# jncc3000.net
KiCad netlist of a schematic drawn in EAGLE
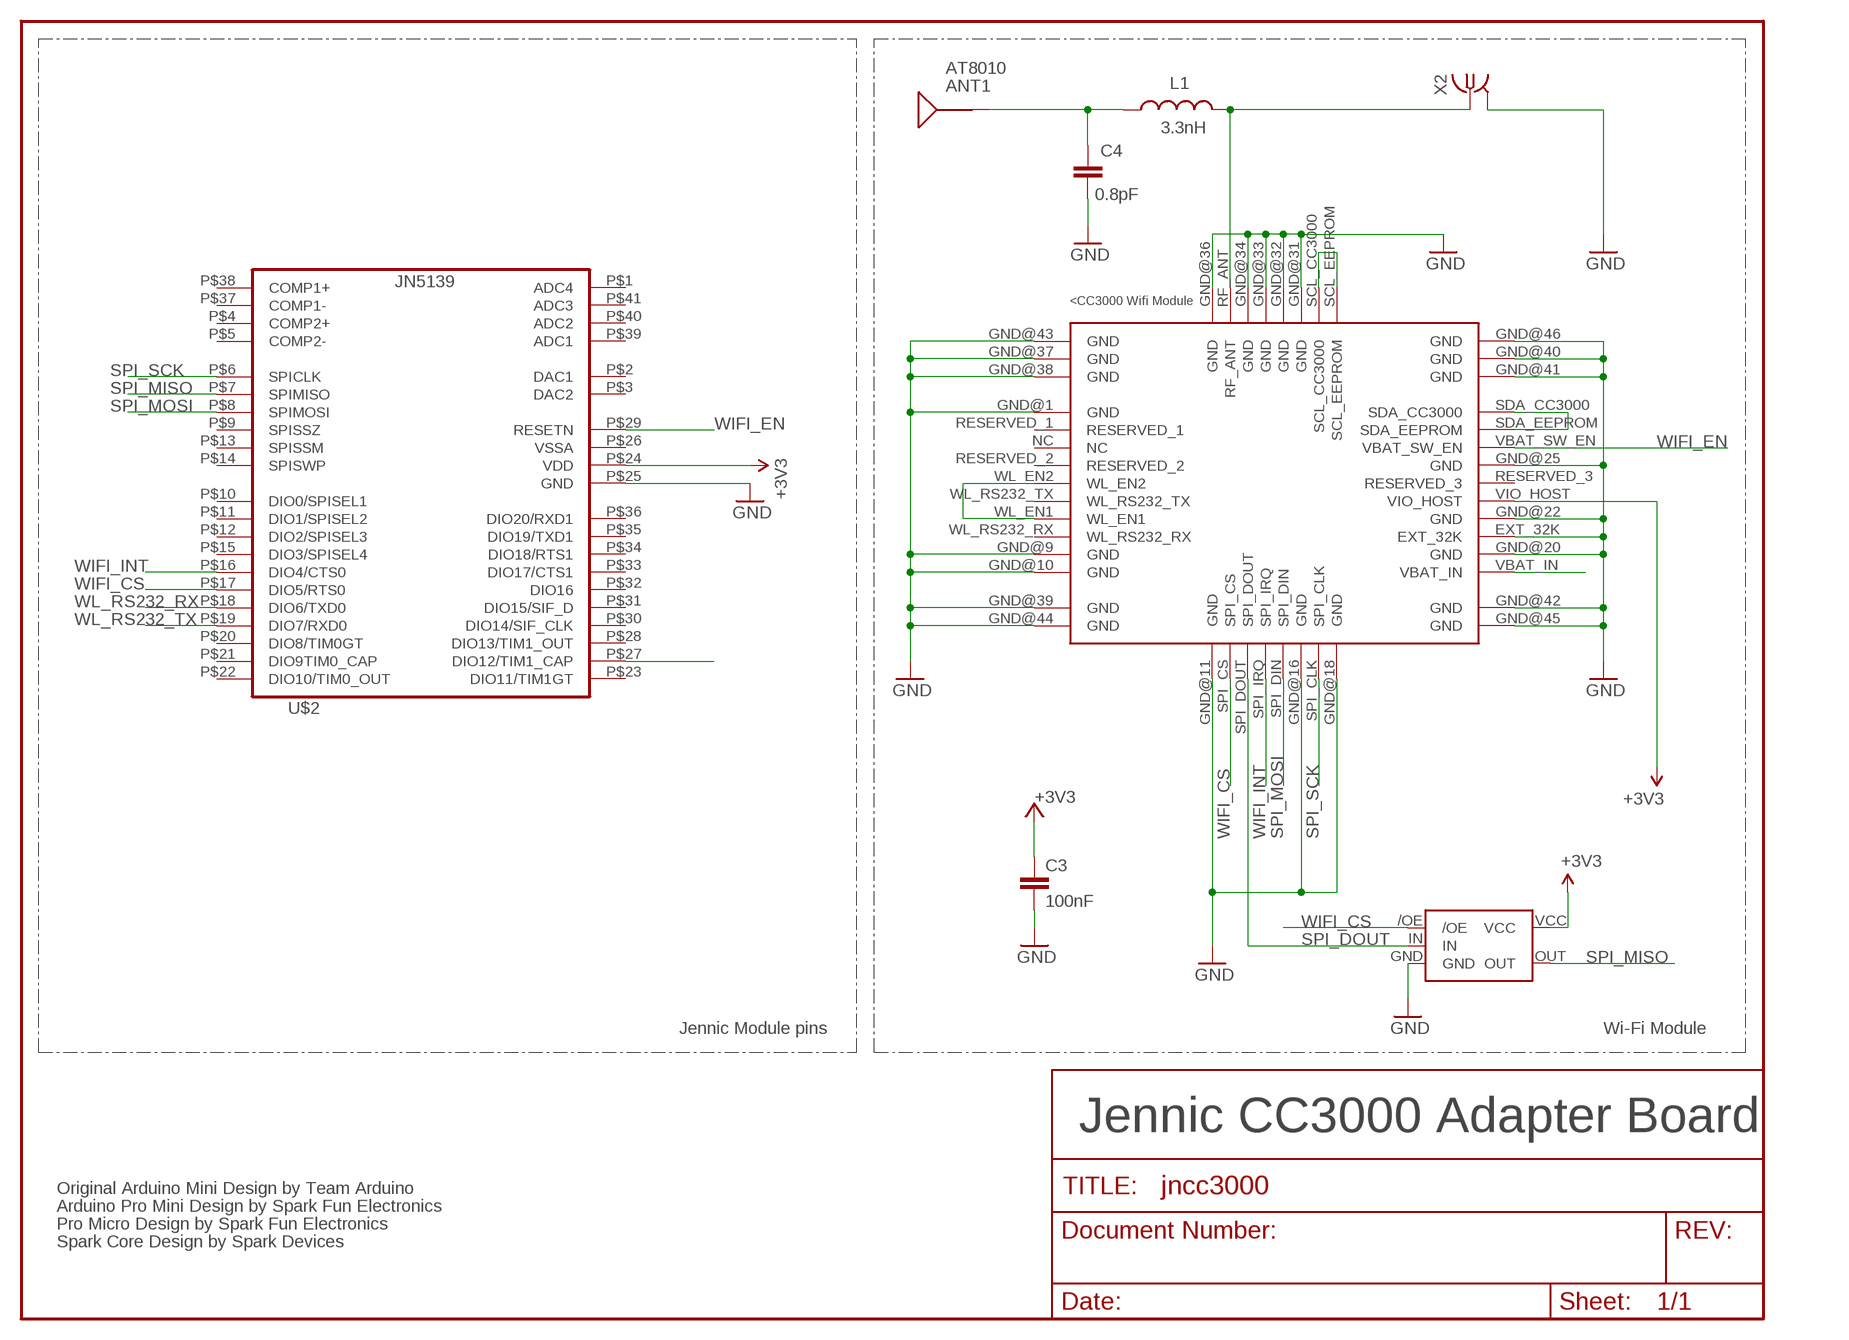
[diagram p0: schematic, sheet 1]

(export (version "E")
  (design (tool "Eeschema 10.0.6"))
  (components
    (comp (ref "ANT1")
      (value "AT8010")
      (footprint "eagle-import:AT8010")
      (libsource (lib "eagle-import") (part "AT8010"))
    )
    (comp (ref "C3")
      (value "100nF")
      (footprint "eagle-import:C0603")
      (libsource (lib "eagle-import") (part "C-EUC0603"))
    )
    (comp (ref "C4")
      (value "0.8pF")
      (footprint "eagle-import:C0603")
      (fields (field (name "COMMENT") "RF Capacitor"))
      (libsource (lib "eagle-import") (part "C-EUC0603"))
    )
    (comp (ref "L1")
      (value "3.3nH")
      (footprint "eagle-import:0603")
      (fields (field (name "COMMENT") "RF Inductor"))
      (libsource (lib "eagle-import") (part "INDUCTOR0603"))
    )
    (comp (ref "U$2")
      (value "JENNIC_JN51XXTH")
      (footprint "eagle-import:JN5139_TH")
      (libsource (lib "eagle-import") (part "JENNIC_JN51XXTH"))
    )
    (comp (ref "U1")
      (value "CC3000")
      (footprint "eagle-import:CC3000")
      (libsource (lib "eagle-import") (part "CC3000"))
    )
    (comp (ref "U4")
      (value "NL17SZ125SOT553")
      (footprint "eagle-import:SOT-553")
      (libsource (lib "eagle-import") (part "NL17SZ125SOT553"))
    )
    (comp (ref "X2")
      (value "IPEX-20279-001E")
      (footprint "eagle-import:IPEX-20279-001E")
      (libsource (lib "eagle-import") (part "IPEX-20279-001E"))
    )
  )
  (nets
    (net (code "1") (name "+3V3") (class "Default")
      (node (ref "C3") (pin "1") (pinfunction "1_1") (pintype "passive"))
      (node (ref "U$2") (pin "P$24") (pinfunction "VDD_P$24") (pintype "bidirectional"))
      (node (ref "U1") (pin "VIO_HOST") (pinfunction "VIO_HOST_VIO_HOST") (pintype "power_in"))
      (node (ref "U4") (pin "VCC") (pinfunction "VCC_VCC") (pintype "bidirectional"))
    )
    (net (code "2") (name "/SPI_DOUT") (class "Default")
      (node (ref "U1") (pin "SPI_DOUT") (pinfunction "SPI_DOUT_SPI_DOUT") (pintype "output"))
      (node (ref "U4") (pin "IN") (pinfunction "IN_IN") (pintype "bidirectional"))
    )
    (net (code "3") (name "/SPI_MISO") (class "Default")
      (node (ref "U$2") (pin "P$7") (pinfunction "SPIMISO_P$7") (pintype "bidirectional"))
      (node (ref "U4") (pin "OUT") (pinfunction "OUT_OUT") (pintype "bidirectional"))
    )
    (net (code "4") (name "/SPI_MOSI") (class "Default")
      (node (ref "U$2") (pin "P$8") (pinfunction "SPIMOSI_P$8") (pintype "bidirectional"))
      (node (ref "U1") (pin "SPI_DIN") (pinfunction "SPI_DIN_SPI_DIN") (pintype "input"))
    )
    (net (code "5") (name "/SPI_SCK") (class "Default")
      (node (ref "U$2") (pin "P$6") (pinfunction "SPICLK_P$6") (pintype "bidirectional"))
      (node (ref "U1") (pin "SPI_CLK") (pinfunction "SPI_CLK_SPI_CLK") (pintype "input"))
    )
    (net (code "6") (name "/VBAT") (class "Default")
      (node (ref "U$2") (pin "P$27") (pinfunction "DIO12/TIM1_CAP_P$27") (pintype "bidirectional"))
      (node (ref "U1") (pin "VBAT_IN") (pinfunction "VBAT_IN_VBAT_IN") (pintype "power_in"))
    )
    (net (code "7") (name "/WIFI_CS") (class "Default")
      (node (ref "U$2") (pin "P$17") (pinfunction "DIO5/RTS0_P$17") (pintype "bidirectional"))
      (node (ref "U1") (pin "SPI_CS") (pinfunction "SPI_CS_SPI_CS") (pintype "input"))
      (node (ref "U4") (pin "/OE") (pinfunction "/OE_/OE") (pintype "bidirectional"))
    )
    (net (code "8") (name "/WIFI_EN") (class "Default")
      (node (ref "U$2") (pin "P$29") (pinfunction "RESETN_P$29") (pintype "bidirectional"))
      (node (ref "U1") (pin "VBAT_SW_EN") (pinfunction "VBAT_SW_EN_VBAT_SW_EN") (pintype "input"))
    )
    (net (code "9") (name "/WIFI_INT") (class "Default")
      (node (ref "U$2") (pin "P$16") (pinfunction "DIO4/CTS0_P$16") (pintype "bidirectional"))
      (node (ref "U1") (pin "SPI_IRQ") (pinfunction "SPI_IRQ_SPI_IRQ") (pintype "output"))
    )
    (net (code "10") (name "/WL_RS232_RX") (class "Default")
      (node (ref "U$2") (pin "P$18") (pinfunction "DIO6/TXD0_P$18") (pintype "bidirectional"))
    )
    (net (code "11") (name "/WL_RS232_TX") (class "Default")
      (node (ref "U$2") (pin "P$19") (pinfunction "DIO7/RXD0_P$19") (pintype "bidirectional"))
    )
    (net (code "12") (name "GND") (class "Default")
      (node (ref "C3") (pin "2") (pinfunction "2_2") (pintype "passive"))
      (node (ref "C4") (pin "2") (pinfunction "2_2") (pintype "passive"))
      (node (ref "U$2") (pin "P$25") (pinfunction "GND_P$25") (pintype "bidirectional"))
      (node (ref "U1") (pin "EXT_32K") (pinfunction "EXT_32K_EXT_32K") (pintype "bidirectional"))
      (node (ref "U1") (pin "GND@1") (pinfunction "GND_GND@1") (pintype "power_in"))
      (node (ref "U1") (pin "GND@10") (pinfunction "GND_GND@10") (pintype "power_in"))
      (node (ref "U1") (pin "GND@11") (pinfunction "GND_GND@11") (pintype "power_in"))
      (node (ref "U1") (pin "GND@16") (pinfunction "GND_GND@16") (pintype "power_in"))
      (node (ref "U1") (pin "GND@18") (pinfunction "GND_GND@18") (pintype "power_in"))
      (node (ref "U1") (pin "GND@20") (pinfunction "GND_GND@20") (pintype "power_in"))
      (node (ref "U1") (pin "GND@22") (pinfunction "GND_GND@22") (pintype "power_in"))
      (node (ref "U1") (pin "GND@25") (pinfunction "GND_GND@25") (pintype "power_in"))
      (node (ref "U1") (pin "GND@31") (pinfunction "GND_GND@31") (pintype "power_in"))
      (node (ref "U1") (pin "GND@32") (pinfunction "GND_GND@32") (pintype "power_in"))
      (node (ref "U1") (pin "GND@33") (pinfunction "GND_GND@33") (pintype "power_in"))
      (node (ref "U1") (pin "GND@34") (pinfunction "GND_GND@34") (pintype "power_in"))
      (node (ref "U1") (pin "GND@36") (pinfunction "GND_GND@36") (pintype "power_in"))
      (node (ref "U1") (pin "GND@37") (pinfunction "GND_GND@37") (pintype "power_in"))
      (node (ref "U1") (pin "GND@38") (pinfunction "GND_GND@38") (pintype "power_in"))
      (node (ref "U1") (pin "GND@39") (pinfunction "GND_GND@39") (pintype "power_in"))
      (node (ref "U1") (pin "GND@40") (pinfunction "GND_GND@40") (pintype "power_in"))
      (node (ref "U1") (pin "GND@41") (pinfunction "GND_GND@41") (pintype "power_in"))
      (node (ref "U1") (pin "GND@42") (pinfunction "GND_GND@42") (pintype "power_in"))
      (node (ref "U1") (pin "GND@43") (pinfunction "GND_GND@43") (pintype "power_in"))
      (node (ref "U1") (pin "GND@44") (pinfunction "GND_GND@44") (pintype "power_in"))
      (node (ref "U1") (pin "GND@45") (pinfunction "GND_GND@45") (pintype "power_in"))
      (node (ref "U1") (pin "GND@46") (pinfunction "GND_GND@46") (pintype "power_in"))
      (node (ref "U1") (pin "GND@9") (pinfunction "GND_GND@9") (pintype "power_in"))
      (node (ref "U4") (pin "GND") (pinfunction "GND_GND") (pintype "bidirectional"))
      (node (ref "X2") (pin "2@1") (pinfunction "GND_2@1") (pintype "passive"))
      (node (ref "X2") (pin "2@2") (pinfunction "GND_2@2") (pintype "passive"))
    )
    (net (code "13") (name "Net-(ANT1-SIGNAL)") (class "Default")
      (node (ref "ANT1") (pin "SIG") (pinfunction "SIGNAL_SIG") (pintype "bidirectional"))
      (node (ref "C4") (pin "1") (pinfunction "1_1") (pintype "passive"))
      (node (ref "L1") (pin "1") (pinfunction "1_1") (pintype "passive"))
    )
    (net (code "14") (name "Net-(L1-Pad2)") (class "Default")
      (node (ref "L1") (pin "2") (pinfunction "2_2") (pintype "passive"))
      (node (ref "U1") (pin "RF_ANT") (pinfunction "RF_ANT_RF_ANT") (pintype "bidirectional"))
      (node (ref "X2") (pin "1") (pinfunction "1_1") (pintype "passive"))
    )
    (net (code "15") (name "Net-(U1-PadSCL_CC3000)") (class "Default")
      (node (ref "U1") (pin "SCL_CC3000") (pinfunction "SCL_CC3000_SCL_CC3000") (pintype "bidirectional"))
      (node (ref "U1") (pin "SCL_EEPROM") (pinfunction "SCL_EEPROM_SCL_EEPROM") (pintype "bidirectional"))
    )
    (net (code "16") (name "Net-(U1-PadSDA_CC3000)") (class "Default")
      (node (ref "U1") (pin "SDA_CC3000") (pinfunction "SDA_CC3000_SDA_CC3000") (pintype "bidirectional"))
      (node (ref "U1") (pin "SDA_EEPROM") (pinfunction "SDA_EEPROM_SDA_EEPROM") (pintype "bidirectional"))
    )
    (net (code "17") (name "Net-(U1-PadWL_EN1)") (class "Default")
      (node (ref "U1") (pin "WL_EN1") (pinfunction "WL_EN1_WL_EN1") (pintype "input"))
      (node (ref "U1") (pin "WL_EN2") (pinfunction "WL_EN2_WL_EN2") (pintype "input"))
    )
    (net (code "18") (name "unconnected-(U$2-ADC1-PadP$39)") (class "Default")
      (node (ref "U$2") (pin "P$39") (pinfunction "ADC1_P$39") (pintype "bidirectional"))
    )
    (net (code "19") (name "unconnected-(U$2-ADC2-PadP$40)") (class "Default")
      (node (ref "U$2") (pin "P$40") (pinfunction "ADC2_P$40") (pintype "bidirectional"))
    )
    (net (code "20") (name "unconnected-(U$2-ADC3-PadP$41)") (class "Default")
      (node (ref "U$2") (pin "P$41") (pinfunction "ADC3_P$41") (pintype "bidirectional"))
    )
    (net (code "21") (name "unconnected-(U$2-ADC4-PadP$1)") (class "Default")
      (node (ref "U$2") (pin "P$1") (pinfunction "ADC4_P$1") (pintype "bidirectional"))
    )
    (net (code "22") (name "unconnected-(U$2-COMP1+-PadP$38)") (class "Default")
      (node (ref "U$2") (pin "P$38") (pinfunction "COMP1+_P$38") (pintype "bidirectional"))
    )
    (net (code "23") (name "unconnected-(U$2-COMP1--PadP$37)") (class "Default")
      (node (ref "U$2") (pin "P$37") (pinfunction "COMP1-_P$37") (pintype "bidirectional"))
    )
    (net (code "24") (name "unconnected-(U$2-COMP2+-PadP$4)") (class "Default")
      (node (ref "U$2") (pin "P$4") (pinfunction "COMP2+_P$4") (pintype "bidirectional"))
    )
    (net (code "25") (name "unconnected-(U$2-COMP2--PadP$5)") (class "Default")
      (node (ref "U$2") (pin "P$5") (pinfunction "COMP2-_P$5") (pintype "bidirectional"))
    )
    (net (code "26") (name "unconnected-(U$2-DAC1-PadP$2)") (class "Default")
      (node (ref "U$2") (pin "P$2") (pinfunction "DAC1_P$2") (pintype "bidirectional"))
    )
    (net (code "27") (name "unconnected-(U$2-DAC2-PadP$3)") (class "Default")
      (node (ref "U$2") (pin "P$3") (pinfunction "DAC2_P$3") (pintype "bidirectional"))
    )
    (net (code "28") (name "unconnected-(U$2-DIO0{slash}SPISEL1-PadP$10)") (class "Default")
      (node (ref "U$2") (pin "P$10") (pinfunction "DIO0/SPISEL1_P$10") (pintype "bidirectional"))
    )
    (net (code "29") (name "unconnected-(U$2-DIO1{slash}SPISEL2-PadP$11)") (class "Default")
      (node (ref "U$2") (pin "P$11") (pinfunction "DIO1/SPISEL2_P$11") (pintype "bidirectional"))
    )
    (net (code "30") (name "unconnected-(U$2-DIO2{slash}SPISEL3-PadP$12)") (class "Default")
      (node (ref "U$2") (pin "P$12") (pinfunction "DIO2/SPISEL3_P$12") (pintype "bidirectional"))
    )
    (net (code "31") (name "unconnected-(U$2-DIO3{slash}SPISEL4-PadP$15)") (class "Default")
      (node (ref "U$2") (pin "P$15") (pinfunction "DIO3/SPISEL4_P$15") (pintype "bidirectional"))
    )
    (net (code "32") (name "unconnected-(U$2-DIO8{slash}TIM0GT-PadP$20)") (class "Default")
      (node (ref "U$2") (pin "P$20") (pinfunction "DIO8/TIM0GT_P$20") (pintype "bidirectional"))
    )
    (net (code "33") (name "unconnected-(U$2-DIO9TIM0_CAP-PadP$21)") (class "Default")
      (node (ref "U$2") (pin "P$21") (pinfunction "DIO9TIM0_CAP_P$21") (pintype "bidirectional"))
    )
    (net (code "34") (name "unconnected-(U$2-DIO10{slash}TIM0_OUT-PadP$22)") (class "Default")
      (node (ref "U$2") (pin "P$22") (pinfunction "DIO10/TIM0_OUT_P$22") (pintype "bidirectional"))
    )
    (net (code "35") (name "unconnected-(U$2-DIO11{slash}TIM1GT-PadP$23)") (class "Default")
      (node (ref "U$2") (pin "P$23") (pinfunction "DIO11/TIM1GT_P$23") (pintype "bidirectional"))
    )
    (net (code "36") (name "unconnected-(U$2-DIO13{slash}TIM1_OUT-PadP$28)") (class "Default")
      (node (ref "U$2") (pin "P$28") (pinfunction "DIO13/TIM1_OUT_P$28") (pintype "bidirectional"))
    )
    (net (code "37") (name "unconnected-(U$2-DIO14{slash}SIF_CLK-PadP$30)") (class "Default")
      (node (ref "U$2") (pin "P$30") (pinfunction "DIO14/SIF_CLK_P$30") (pintype "bidirectional"))
    )
    (net (code "38") (name "unconnected-(U$2-DIO15{slash}SIF_D-PadP$31)") (class "Default")
      (node (ref "U$2") (pin "P$31") (pinfunction "DIO15/SIF_D_P$31") (pintype "bidirectional"))
    )
    (net (code "39") (name "unconnected-(U$2-DIO16-PadP$32)") (class "Default")
      (node (ref "U$2") (pin "P$32") (pinfunction "DIO16_P$32") (pintype "bidirectional"))
    )
    (net (code "40") (name "unconnected-(U$2-DIO17{slash}CTS1-PadP$33)") (class "Default")
      (node (ref "U$2") (pin "P$33") (pinfunction "DIO17/CTS1_P$33") (pintype "bidirectional"))
    )
    (net (code "41") (name "unconnected-(U$2-DIO18{slash}RTS1-PadP$34)") (class "Default")
      (node (ref "U$2") (pin "P$34") (pinfunction "DIO18/RTS1_P$34") (pintype "bidirectional"))
    )
    (net (code "42") (name "unconnected-(U$2-DIO19{slash}TXD1-PadP$35)") (class "Default")
      (node (ref "U$2") (pin "P$35") (pinfunction "DIO19/TXD1_P$35") (pintype "bidirectional"))
    )
    (net (code "43") (name "unconnected-(U$2-DIO20{slash}RXD1-PadP$36)") (class "Default")
      (node (ref "U$2") (pin "P$36") (pinfunction "DIO20/RXD1_P$36") (pintype "bidirectional"))
    )
    (net (code "44") (name "unconnected-(U$2-SPISSM-PadP$13)") (class "Default")
      (node (ref "U$2") (pin "P$13") (pinfunction "SPISSM_P$13") (pintype "bidirectional"))
    )
    (net (code "45") (name "unconnected-(U$2-SPISSZ-PadP$9)") (class "Default")
      (node (ref "U$2") (pin "P$9") (pinfunction "SPISSZ_P$9") (pintype "bidirectional"))
    )
    (net (code "46") (name "unconnected-(U$2-SPISWP-PadP$14)") (class "Default")
      (node (ref "U$2") (pin "P$14") (pinfunction "SPISWP_P$14") (pintype "bidirectional"))
    )
    (net (code "47") (name "unconnected-(U$2-VSSA-PadP$26)") (class "Default")
      (node (ref "U$2") (pin "P$26") (pinfunction "VSSA_P$26") (pintype "bidirectional"))
    )
    (net (code "48") (name "unconnected-(U1-PadNC)") (class "Default")
      (node (ref "U1") (pin "NC") (pinfunction "NC_NC") (pintype "no_connect"))
    )
    (net (code "49") (name "unconnected-(U1-PadRESERVED_1)") (class "Default")
      (node (ref "U1") (pin "RESERVED_1") (pinfunction "RESERVED_1_RESERVED_1") (pintype "bidirectional"))
    )
    (net (code "50") (name "unconnected-(U1-PadRESERVED_2)") (class "Default")
      (node (ref "U1") (pin "RESERVED_2") (pinfunction "RESERVED_2_RESERVED_2") (pintype "bidirectional"))
    )
    (net (code "51") (name "unconnected-(U1-PadRESERVED_3)") (class "Default")
      (node (ref "U1") (pin "RESERVED_3") (pinfunction "RESERVED_3_RESERVED_3") (pintype "bidirectional"))
    )
    (net (code "52") (name "unconnected-(U1-PadWL_RS232_RX)") (class "Default")
      (node (ref "U1") (pin "WL_RS232_RX") (pinfunction "WL_RS232_RX_WL_RS232_RX") (pintype "input"))
    )
    (net (code "53") (name "unconnected-(U1-PadWL_RS232_TX)") (class "Default")
      (node (ref "U1") (pin "WL_RS232_TX") (pinfunction "WL_RS232_TX_WL_RS232_TX") (pintype "output"))
    )
  )
)
